# SWITCHES.net
KiCad netlist of a schematic drawn in Altium Designer
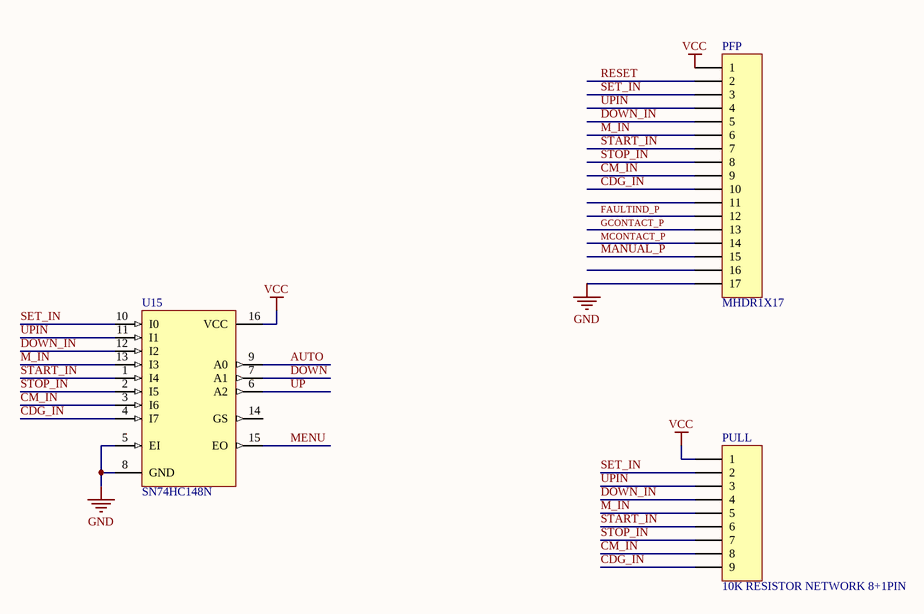
[diagram p0: SWITCHES.SchDoc]

(export (version "E")
  (design (tool "Eeschema 10.0.6"))
  (components
    (comp (ref "PFP")
      (value "MHDR1X17")
      (footprint "HDR1X17_BURGE_F")
      (description "Header, 17-Pin")
      (fields (field (name "PUBLISHER") "Altium Limited"))
      (libsource (lib "Miscellaneous Connectors") (part "MHDR1X17"))
    )
    (comp (ref "PULL")
      (value "10K RESISTOR NETWORK 8+1PIN")
      (footprint "RESPACK8+1")
      (description "Header, 9-Pin")
      (fields (field (name "PUBLISHER") "Altium Limited"))
      (libsource (lib "Miscellaneous Connectors") (part "Header 9"))
    )
    (comp (ref "U15")
      (value "SN74HC148N")
      (footprint "N016D")
      (description "8-Line to 3-Line Priority Encoder")
      (fields (field (name "PUBLISHER") "Altium Limited"))
      (libsource (lib "TI Logic Multiplexer") (part "SN74HC148N"))
    )
  )
  (nets
    (net (code "1") (name "/AUTO") (class "Default")
      (node (ref "U15") (pin "9") (pinfunction "A0_9") (pintype "output"))
    )
    (net (code "2") (name "/CDG_IN") (class "Default")
      (node (ref "PFP") (pin "10") (pinfunction "10_10") (pintype "passive"))
      (node (ref "PULL") (pin "9") (pinfunction "9_9") (pintype "passive"))
      (node (ref "U15") (pin "4") (pinfunction "I7_4") (pintype "input"))
    )
    (net (code "3") (name "/CM_IN") (class "Default")
      (node (ref "PFP") (pin "9") (pinfunction "9_9") (pintype "passive"))
      (node (ref "PULL") (pin "8") (pinfunction "8_8") (pintype "passive"))
      (node (ref "U15") (pin "3") (pinfunction "I6_3") (pintype "input"))
    )
    (net (code "4") (name "/DOWN") (class "Default")
      (node (ref "U15") (pin "7") (pinfunction "A1_7") (pintype "output"))
    )
    (net (code "5") (name "/DOWN_IN") (class "Default")
      (node (ref "PFP") (pin "5") (pinfunction "5_5") (pintype "passive"))
      (node (ref "PULL") (pin "4") (pinfunction "4_4") (pintype "passive"))
      (node (ref "U15") (pin "12") (pinfunction "I2_12") (pintype "input"))
    )
    (net (code "6") (name "/FAULTIND_P") (class "Default")
      (node (ref "PFP") (pin "12") (pinfunction "12_12") (pintype "passive"))
    )
    (net (code "7") (name "/GCONTACT_P") (class "Default")
      (node (ref "PFP") (pin "13") (pinfunction "13_13") (pintype "passive"))
    )
    (net (code "8") (name "/MANUAL_P") (class "Default")
      (node (ref "PFP") (pin "15") (pinfunction "15_15") (pintype "passive"))
    )
    (net (code "9") (name "/MCONTACT_P") (class "Default")
      (node (ref "PFP") (pin "14") (pinfunction "14_14") (pintype "passive"))
    )
    (net (code "10") (name "/MENU") (class "Default")
      (node (ref "U15") (pin "15") (pinfunction "EO_15") (pintype "output"))
    )
    (net (code "11") (name "/M_IN") (class "Default")
      (node (ref "PFP") (pin "6") (pinfunction "6_6") (pintype "passive"))
      (node (ref "PULL") (pin "5") (pinfunction "5_5") (pintype "passive"))
      (node (ref "U15") (pin "13") (pinfunction "I3_13") (pintype "input"))
    )
    (net (code "12") (name "/RESET") (class "Default")
      (node (ref "PFP") (pin "2") (pinfunction "2_2") (pintype "passive"))
    )
    (net (code "13") (name "/SET_IN") (class "Default")
      (node (ref "PFP") (pin "3") (pinfunction "3_3") (pintype "passive"))
      (node (ref "PULL") (pin "2") (pinfunction "2_2") (pintype "passive"))
      (node (ref "U15") (pin "10") (pinfunction "I0_10") (pintype "input"))
    )
    (net (code "14") (name "/START_IN") (class "Default")
      (node (ref "PFP") (pin "7") (pinfunction "7_7") (pintype "passive"))
      (node (ref "PULL") (pin "6") (pinfunction "6_6") (pintype "passive"))
      (node (ref "U15") (pin "1") (pinfunction "I4_1") (pintype "input"))
    )
    (net (code "15") (name "/STOP_IN") (class "Default")
      (node (ref "PFP") (pin "8") (pinfunction "8_8") (pintype "passive"))
      (node (ref "PULL") (pin "7") (pinfunction "7_7") (pintype "passive"))
      (node (ref "U15") (pin "2") (pinfunction "I5_2") (pintype "input"))
    )
    (net (code "16") (name "/UP") (class "Default")
      (node (ref "U15") (pin "6") (pinfunction "A2_6") (pintype "output"))
    )
    (net (code "17") (name "/UPIN") (class "Default")
      (node (ref "PFP") (pin "4") (pinfunction "4_4") (pintype "passive"))
      (node (ref "PULL") (pin "3") (pinfunction "3_3") (pintype "passive"))
      (node (ref "U15") (pin "11") (pinfunction "I1_11") (pintype "input"))
    )
    (net (code "18") (name "GND") (class "Default")
      (node (ref "PFP") (pin "17") (pinfunction "17_17") (pintype "passive"))
      (node (ref "U15") (pin "5") (pinfunction "EI_5") (pintype "input"))
      (node (ref "U15") (pin "8") (pinfunction "GND_8") (pintype "power_in"))
    )
    (net (code "19") (name "VCC") (class "Default")
      (node (ref "PFP") (pin "1") (pinfunction "1_1") (pintype "passive"))
      (node (ref "PULL") (pin "1") (pinfunction "1_1") (pintype "passive"))
      (node (ref "U15") (pin "16") (pinfunction "VCC_16") (pintype "power_in"))
    )
    (net (code "20") (name "unconnected-(PFP-Pad11)") (class "Default")
      (node (ref "PFP") (pin "11") (pinfunction "11_11") (pintype "passive"))
    )
    (net (code "21") (name "unconnected-(PFP-Pad16)") (class "Default")
      (node (ref "PFP") (pin "16") (pinfunction "16_16") (pintype "passive"))
    )
    (net (code "22") (name "unconnected-(U15-GS-Pad14)") (class "Default")
      (node (ref "U15") (pin "14") (pinfunction "GS_14") (pintype "output"))
    )
  )
)
